# Capacitance_Sensing.net
KiCad netlist of a schematic drawn in Altium Designer
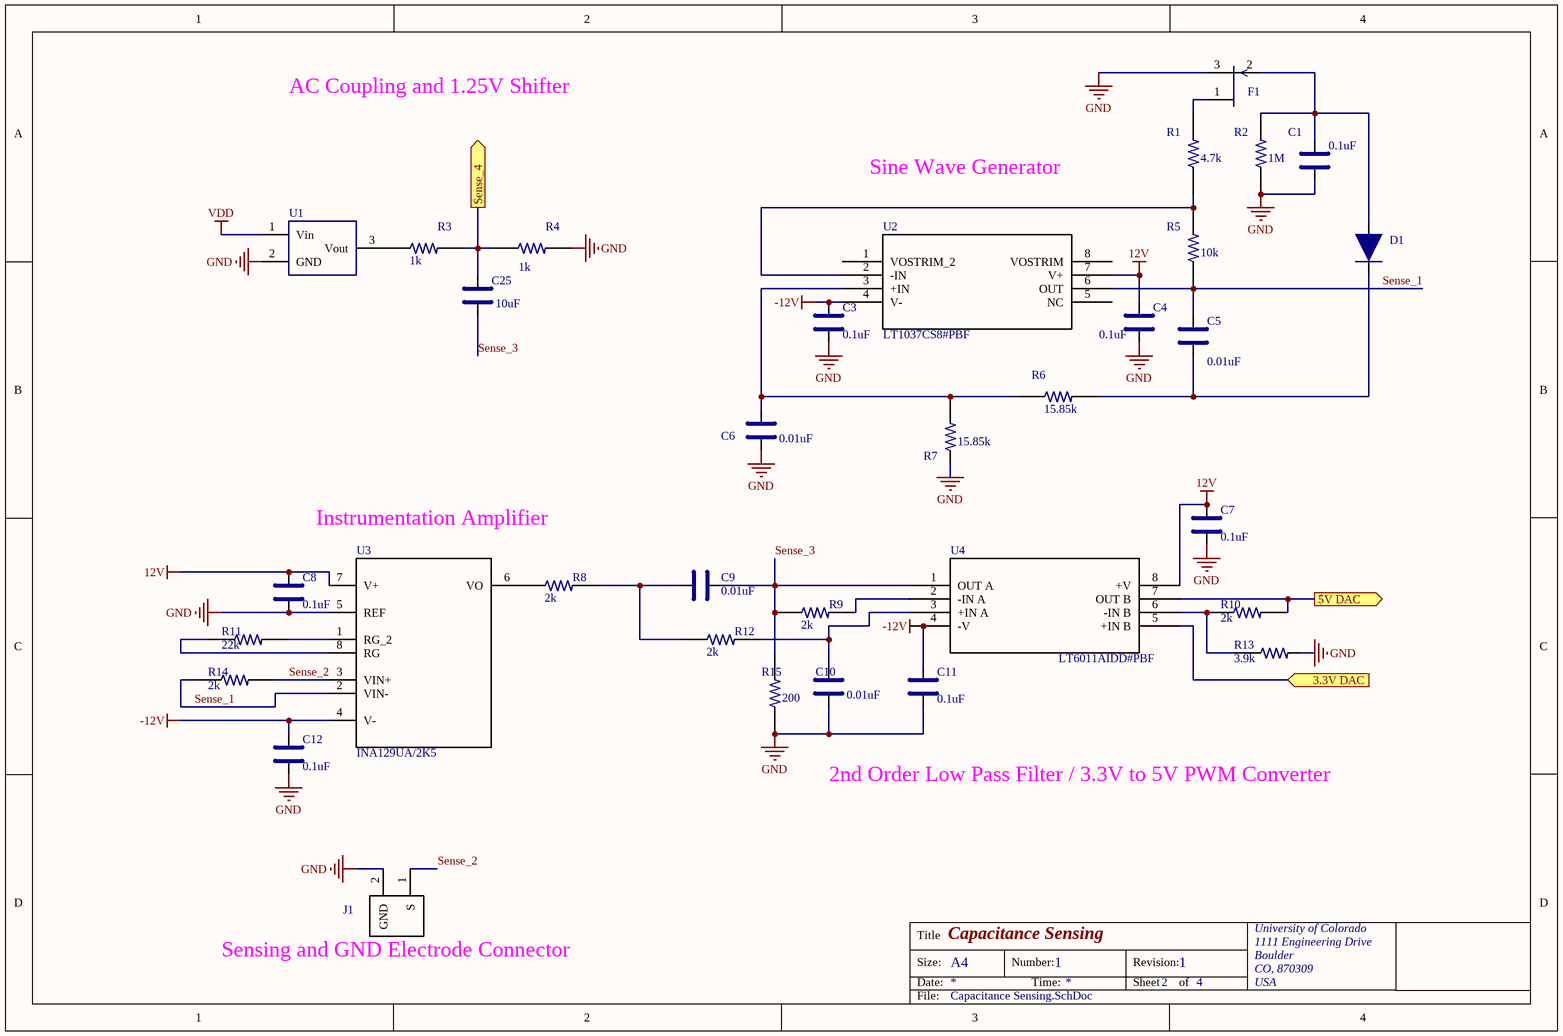
[diagram p0: Capacitance Sensing.SchDoc]

(export (version "E")
  (design (tool "Eeschema 10.0.6"))
  (components
    (comp (ref "C1")
      (value "0.1uF")
      (footprint "CL03A104KA3NNNC")
      (description "CAP CER 0.1UF 25V X5R 0201")
      (fields
        (field (name "MANUFACTURER") "Samsung")
        (field (name "MANUFACTURER PART NUMBER") "CL03A104KA3NNNC")
      )
      (libsource (lib "Sensing PEANO_Library") (part "CL03A104KA3NNNC"))
    )
    (comp (ref "C3")
      (value "0.1uF")
      (footprint "CL03A104KA3NNNC")
      (description "CAP CER 0.1UF 25V X5R 0201")
      (fields
        (field (name "MANUFACTURER") "Samsung")
        (field (name "MANUFACTURER PART NUMBER") "CL03A104KA3NNNC")
      )
      (libsource (lib "Sensing PEANO_Library") (part "CL03A104KA3NNNC"))
    )
    (comp (ref "C4")
      (value "0.1uF")
      (footprint "CL03A104KA3NNNC")
      (description "CAP CER 0.1UF 25V X5R 0201")
      (fields
        (field (name "MANUFACTURER") "Samsung")
        (field (name "MANUFACTURER PART NUMBER") "CL03A104KA3NNNC")
      )
      (libsource (lib "Sensing PEANO_Library") (part "CL03A104KA3NNNC"))
    )
    (comp (ref "C5")
      (value "0.01uF")
      (footprint "CL03B103KP3NNNC")
      (description "CAP CER 10000PF 10V X7R 0201")
      (fields
        (field (name "MANUFACTURER") "Samsung")
        (field (name "MANUFACTURER PART NUMBER") "CL03B103KP3NNNC")
      )
      (libsource (lib "Sensing PEANO_Library") (part "CL03B103KP3NNNC"))
    )
    (comp (ref "C6")
      (value "0.01uF")
      (footprint "CL03B103KP3NNNC")
      (description "CAP CER 10000PF 10V X7R 0201")
      (fields
        (field (name "MANUFACTURER") "Samsung")
        (field (name "MANUFACTURER PART NUMBER") "CL03B103KP3NNNC")
      )
      (libsource (lib "Sensing PEANO_Library") (part "CL03B103KP3NNNC"))
    )
    (comp (ref "C7")
      (value "0.1uF")
      (footprint "CL03A104KA3NNNC")
      (description "CAP CER 0.1UF 25V X5R 0201")
      (fields
        (field (name "MANUFACTURER") "Samsung")
        (field (name "MANUFACTURER PART NUMBER") "CL03A104KA3NNNC")
      )
      (libsource (lib "Sensing PEANO_Library") (part "CL03A104KA3NNNC"))
    )
    (comp (ref "C8")
      (value "0.1uF")
      (footprint "CL03A104KA3NNNC")
      (description "CAP CER 0.1UF 25V X5R 0201")
      (fields
        (field (name "MANUFACTURER") "Samsung")
        (field (name "MANUFACTURER PART NUMBER") "CL03A104KA3NNNC")
      )
      (libsource (lib "Sensing PEANO_Library") (part "CL03A104KA3NNNC"))
    )
    (comp (ref "C9")
      (value "0.01uF")
      (footprint "CL03B103KP3NNNC")
      (description "CAP CER 10000PF 10V X7R 0201")
      (fields
        (field (name "MANUFACTURER") "Samsung")
        (field (name "MANUFACTURER PART NUMBER") "CL03B103KP3NNNC")
      )
      (libsource (lib "Sensing PEANO_Library") (part "CL03B103KP3NNNC"))
    )
    (comp (ref "C10")
      (value "0.01uF")
      (footprint "CL03B103KP3NNNC")
      (description "CAP CER 10000PF 10V X7R 0201")
      (fields
        (field (name "MANUFACTURER") "Samsung")
        (field (name "MANUFACTURER PART NUMBER") "CL03B103KP3NNNC")
      )
      (libsource (lib "Sensing PEANO_Library") (part "CL03B103KP3NNNC"))
    )
    (comp (ref "C11")
      (value "0.1uF")
      (footprint "CL03A104KA3NNNC")
      (description "CAP CER 0.1UF 25V X5R 0201")
      (fields
        (field (name "MANUFACTURER") "Samsung")
        (field (name "MANUFACTURER PART NUMBER") "CL03A104KA3NNNC")
      )
      (libsource (lib "Sensing PEANO_Library") (part "CL03A104KA3NNNC"))
    )
    (comp (ref "C12")
      (value "0.1uF")
      (footprint "CL03A104KA3NNNC")
      (description "CAP CER 0.1UF 25V X5R 0201")
      (fields
        (field (name "MANUFACTURER") "Samsung")
        (field (name "MANUFACTURER PART NUMBER") "CL03A104KA3NNNC")
      )
      (libsource (lib "Sensing PEANO_Library") (part "CL03A104KA3NNNC"))
    )
    (comp (ref "C25")
      (value "10uF")
      (footprint "GRM155R60J106ME47D")
      (description "CAP CER 10UF 6.3V X5R 0402")
      (fields
        (field (name "MANUFACTURER") "Murata")
        (field (name "MANUFACTURER PART NUMBER") "GRM155R60J106ME47D")
      )
      (libsource (lib "Sensing PEANO_Library") (part "GRM155R60J106ME47D"))
    )
    (comp (ref "D1")
      (value "1N4148W-7-F")
      (footprint "1N4148W-7-F")
      (description "DIODE GEN PURP 100V 300MA SOD123")
      (fields
        (field (name "MANUFACTURER") "Diodes Incorporated")
        (field (name "DIGIKEY PART NUMBER") "1N4148W-FDICT-ND")
      )
      (libsource (lib "Sensing PEANO_Library") (part "1N4148W-7-F"))
    )
    (comp (ref "F1")
      (value "U309")
      (footprint "U309")
      (description "JFET JFET N-Channel -25V 20mA 500mW 4mW")
      (fields (field (name "MANUFACTURER") "InterFET") (field (name "DIGIKEY PART NUMBER") "106-U309"))
      (libsource (lib "Sensing PEANO_Library") (part "U309"))
    )
    (comp (ref "J1")
      (value "SM02B-SRSS-TB")
      (footprint "SM02B-SRSS-TB(LF)(SN)")
      (description "SH Series 2 Position 1 mm Pitch Surface Mount Side Entry Shrouded Header")
      (fields (field (name "MP") "SM02B-SRSS-TB_LF__SN_") (field (name "MF") "JST"))
      (libsource (lib "Sensing PEANO_Library") (part "SM02B-SRSS-TB(LF)(SN)"))
    )
    (comp (ref "R1")
      (value "4.7k")
      (footprint "RC0603J472CS")
      (description "RES SMD 4.7K OHM 5% 1/20W 0201")
      (fields
        (field (name "MANUFACTURER") "Samsung")
        (field (name "MANUFACTURER PART NUMBER") "RC0603J472CS")
      )
      (libsource (lib "Sensing PEANO_Library") (part "RC0603J472CS"))
    )
    (comp (ref "R2")
      (value "1M")
      (footprint "AC0201FR-071ML")
      (description "RES SMD 1M OHM 1% 1/20W 0201")
      (fields
        (field (name "MANUFACTURER") "Yageo")
        (field (name "MANUFACTURER PART NUMBER") "AC0201FR-071ML")
      )
      (libsource (lib "Sensing PEANO_Library") (part "AC0201FR-071ML"))
    )
    (comp (ref "R3")
      (value "1k")
      (footprint "RC0201FR-07130KL")
      (description "RES SMD 130K OHM 1% 1/20W 0201")
      (fields
        (field (name "MANUFACTURER") "Yageo")
        (field (name "MANUFACTURER PART NUMBER") "RC0201FR-07130KL")
      )
      (libsource (lib "Sensing PEANO_Library") (part "RC0201FR-07130KL"))
    )
    (comp (ref "R4")
      (value "1k")
      (footprint "RC0201FR-07130KL")
      (description "RES SMD 130K OHM 1% 1/20W 0201")
      (fields
        (field (name "MANUFACTURER") "Yageo")
        (field (name "MANUFACTURER PART NUMBER") "RC0201FR-07130KL")
      )
      (libsource (lib "Sensing PEANO_Library") (part "RC0201FR-07130KL"))
    )
    (comp (ref "R5")
      (value "10k")
      (footprint "RC0603F103CS")
      (description "RES SMD 10K OHM 1% 1/20W 0201")
      (fields
        (field (name "MANUFACTURER") "Samsung")
        (field (name "MANUFACTURER PART NUMBER") "RC0603F103CS")
      )
      (libsource (lib "Sensing PEANO_Library") (part "RC0603F103CS"))
    )
    (comp (ref "R6")
      (value "15.85k")
      (footprint "RMCF0201FT15K8")
      (description "RES 15.8K OHM 1% 1/20W 0201")
      (fields
        (field (name "MANUFACTURER") "Stackpole")
        (field (name "MANUFACTURER PART NUMBER") "RMCF0201FT15K8")
      )
      (libsource (lib "Sensing PEANO_Library") (part "RMCF0201FT15K8"))
    )
    (comp (ref "R7")
      (value "15.85k")
      (footprint "RMCF0201FT15K8")
      (description "RES 15.8K OHM 1% 1/20W 0201")
      (fields
        (field (name "MANUFACTURER") "Stackpole")
        (field (name "MANUFACTURER PART NUMBER") "RMCF0201FT15K8")
      )
      (libsource (lib "Sensing PEANO_Library") (part "RMCF0201FT15K8"))
    )
    (comp (ref "R8")
      (value "2k")
      (footprint "RC0603F202CS")
      (description "RES SMD 2K OHM 1% 1/20W 0201")
      (fields
        (field (name "MANUFACTURER") "Samsung")
        (field (name "MANUFACTURER PART NUMBER") "RC0603F202CS")
      )
      (libsource (lib "Sensing PEANO_Library") (part "RC0603F202CS"))
    )
    (comp (ref "R9")
      (value "2k")
      (footprint "RC0603F202CS")
      (description "RES SMD 2K OHM 1% 1/20W 0201")
      (fields
        (field (name "MANUFACTURER") "Samsung")
        (field (name "MANUFACTURER PART NUMBER") "RC0603F202CS")
      )
      (libsource (lib "Sensing PEANO_Library") (part "RC0603F202CS"))
    )
    (comp (ref "R10")
      (value "2k")
      (footprint "RC0603F202CS")
      (description "RES SMD 2K OHM 1% 1/20W 0201")
      (fields
        (field (name "MANUFACTURER") "Samsung")
        (field (name "MANUFACTURER PART NUMBER") "RC0603F202CS")
      )
      (libsource (lib "Sensing PEANO_Library") (part "RC0603F202CS"))
    )
    (comp (ref "R11")
      (value "22k")
      (footprint "ERJ-1GNJ223C")
      (description "RES SMD 22K OHM 5% 1/20W 0201")
      (fields
        (field (name "MANUFACTURER") "Samsung")
        (field (name "MANUFACTURER PART NUMBER") "ERJ-1GNJ223C")
      )
      (libsource (lib "Sensing PEANO_Library") (part "ERJ-1GNJ223C"))
    )
    (comp (ref "R12")
      (value "2k")
      (footprint "RC0603F202CS")
      (description "RES SMD 2K OHM 1% 1/20W 0201")
      (fields
        (field (name "MANUFACTURER") "Samsung")
        (field (name "MANUFACTURER PART NUMBER") "RC0603F202CS")
      )
      (libsource (lib "Sensing PEANO_Library") (part "RC0603F202CS"))
    )
    (comp (ref "R13")
      (value "3.9k")
      (footprint "RC0603F202CS")
      (description "RES SMD 2K OHM 1% 1/20W 0201")
      (fields
        (field (name "MANUFACTURER") "Samsung")
        (field (name "MANUFACTURER PART NUMBER") "RC0603F202CS")
      )
      (libsource (lib "Sensing PEANO_Library") (part "RC0603F202CS"))
    )
    (comp (ref "R14")
      (value "2k")
      (footprint "RC0603F202CS")
      (description "RES SMD 2K OHM 1% 1/20W 0201")
      (fields
        (field (name "MANUFACTURER") "Samsung")
        (field (name "MANUFACTURER PART NUMBER") "RC0603F202CS")
      )
      (libsource (lib "Sensing PEANO_Library") (part "RC0603F202CS"))
    )
    (comp (ref "R15")
      (value "200")
      (footprint "RC0603F202CS")
      (description "RES SMD 2K OHM 1% 1/20W 0201")
      (fields
        (field (name "MANUFACTURER") "Samsung")
        (field (name "MANUFACTURER PART NUMBER") "RC0603F202CS")
      )
      (libsource (lib "Sensing PEANO_Library") (part "RC0603F202CS"))
    )
    (comp (ref "U1")
      (value "ISL60002BIH325Z-T7A")
      (footprint "ISL60002-25")
      (description "IC VREF SERIES 2.5V SOT23-3")
      (fields
        (field (name "MANUFACTURER") "Renesas Electronics")
        (field (name "MANUFACTURER PART NUMBER") "ISL60002BIH325Z-TK")
      )
      (libsource (lib "Sensing PEANO_Library") (part "ISL60002BIH325Z-T7A"))
    )
    (comp (ref "U2")
      (value "LT1037CS8#PBF")
      (footprint "LT1037CS8#PBF")
      (description "IC OPAMP GP 60MHZ 8SO")
      (fields
        (field (name "MANUFACTURER") "Linear Technology")
        (field (name "DIGIKEY PART NUMBER") "LT1037CS8#PBF-ND")
      )
      (libsource (lib "Sensing PEANO_Library") (part "LT1037CS8#PBF"))
    )
    (comp (ref "U3")
      (value "INA129UA/2K5")
      (footprint "INA129UA/2K5")
      (description "IC OPAMP INSTR 1.3MHZ 8SOIC")
      (fields
        (field (name "MANUFACTURER") "Texas Instruments")
        (field (name "DIGIKEY PART NUMBER") "296-26058-1-ND")
      )
      (libsource (lib "Sensing PEANO_Library") (part "INA129UA/2K5"))
    )
    (comp (ref "U4")
      (value "LT6011AIDD#PBF")
      (footprint "ADP7104ACPZ-3.3-R7")
      (description "IC OPAMP GP 350KHZ RRO 8DFN")
      (fields
        (field (name "MANUFACTURER") "Analog Device")
        (field (name "DIGIKEY PART NUMBER") "LT6011AIDD#PBF-ND")
      )
      (libsource (lib "Sensing PEANO_Library") (part "LT6011AIDD#PBF"))
    )
  )
  (nets
    (net (code "1") (name "-12V") (class "Default")
      (node (ref "C11") (pin "1") (pinfunction "1_1") (pintype "passive"))
      (node (ref "C12") (pin "1") (pinfunction "1_1") (pintype "passive"))
      (node (ref "C3") (pin "1") (pinfunction "1_1") (pintype "passive"))
      (node (ref "U2") (pin "4") (pinfunction "V-_4") (pintype "passive"))
      (node (ref "U3") (pin "4") (pinfunction "V-_4") (pintype "passive"))
      (node (ref "U4") (pin "4") (pinfunction "-V_4") (pintype "passive"))
    )
    (net (code "2") (name "/3.3V DAC") (class "Default")
      (node (ref "U4") (pin "5") (pinfunction "+IN_B_5") (pintype "passive"))
    )
    (net (code "3") (name "/5V DAC") (class "Default")
      (node (ref "R10") (pin "1") (pinfunction "1_1") (pintype "passive"))
      (node (ref "U4") (pin "7") (pinfunction "OUT_B_7") (pintype "passive"))
    )
    (net (code "4") (name "/Sense_1") (class "Default")
      (node (ref "C5") (pin "1") (pinfunction "1_1") (pintype "passive"))
      (node (ref "R14") (pin "2") (pinfunction "2_2") (pintype "passive"))
      (node (ref "R5") (pin "2") (pinfunction "2_2") (pintype "passive"))
      (node (ref "U2") (pin "6") (pinfunction "OUT_6") (pintype "passive"))
      (node (ref "U3") (pin "2") (pinfunction "VIN-_2") (pintype "passive"))
    )
    (net (code "5") (name "/Sense_2") (class "Default")
      (node (ref "J1") (pin "1") (pinfunction "S_1") (pintype "passive"))
      (node (ref "R14") (pin "1") (pinfunction "1_1") (pintype "passive"))
      (node (ref "U3") (pin "3") (pinfunction "VIN+_3") (pintype "passive"))
    )
    (net (code "6") (name "/Sense_3") (class "Default")
      (node (ref "C25") (pin "2") (pinfunction "2_2") (pintype "passive"))
      (node (ref "C9") (pin "1") (pinfunction "1_1") (pintype "passive"))
      (node (ref "R15") (pin "1") (pinfunction "1_1") (pintype "passive"))
      (node (ref "R9") (pin "2") (pinfunction "2_2") (pintype "passive"))
      (node (ref "U4") (pin "1") (pinfunction "OUT_A_1") (pintype "passive"))
    )
    (net (code "7") (name "/Sense_4") (class "Default")
      (node (ref "C25") (pin "1") (pinfunction "1_1") (pintype "passive"))
      (node (ref "R3") (pin "1") (pinfunction "1_1") (pintype "passive"))
      (node (ref "R4") (pin "2") (pinfunction "2_2") (pintype "passive"))
    )
    (net (code "8") (name "12V") (class "Default")
      (node (ref "C4") (pin "1") (pinfunction "1_1") (pintype "passive"))
      (node (ref "C7") (pin "1") (pinfunction "1_1") (pintype "passive"))
      (node (ref "C8") (pin "1") (pinfunction "1_1") (pintype "passive"))
      (node (ref "U2") (pin "7") (pinfunction "V+_7") (pintype "passive"))
      (node (ref "U3") (pin "7") (pinfunction "V+_7") (pintype "passive"))
      (node (ref "U4") (pin "8") (pinfunction "+V_8") (pintype "passive"))
    )
    (net (code "9") (name "GND") (class "Default")
      (node (ref "C1") (pin "2") (pinfunction "2_2") (pintype "passive"))
      (node (ref "C10") (pin "2") (pinfunction "2_2") (pintype "passive"))
      (node (ref "C11") (pin "2") (pinfunction "2_2") (pintype "passive"))
      (node (ref "C12") (pin "2") (pinfunction "2_2") (pintype "passive"))
      (node (ref "C3") (pin "2") (pinfunction "2_2") (pintype "passive"))
      (node (ref "C4") (pin "2") (pinfunction "2_2") (pintype "passive"))
      (node (ref "C6") (pin "2") (pinfunction "2_2") (pintype "passive"))
      (node (ref "C7") (pin "2") (pinfunction "2_2") (pintype "passive"))
      (node (ref "C8") (pin "2") (pinfunction "2_2") (pintype "passive"))
      (node (ref "F1") (pin "3") (pinfunction "S_3") (pintype "passive"))
      (node (ref "J1") (pin "2") (pinfunction "GND_2") (pintype "passive"))
      (node (ref "R13") (pin "1") (pinfunction "1_1") (pintype "passive"))
      (node (ref "R15") (pin "2") (pinfunction "2_2") (pintype "passive"))
      (node (ref "R2") (pin "2") (pinfunction "2_2") (pintype "passive"))
      (node (ref "R4") (pin "1") (pinfunction "1_1") (pintype "passive"))
      (node (ref "R7") (pin "2") (pinfunction "2_2") (pintype "passive"))
      (node (ref "U1") (pin "2") (pinfunction "GND_2") (pintype "passive"))
      (node (ref "U3") (pin "5") (pinfunction "REF_5") (pintype "passive"))
    )
    (net (code "10") (name "Net-(C5-Pad2)") (class "Default")
      (node (ref "C5") (pin "2") (pinfunction "2_2") (pintype "passive"))
      (node (ref "D1") (pin "1") (pinfunction "1_1") (pintype "passive"))
      (node (ref "R6") (pin "1") (pinfunction "1_1") (pintype "passive"))
    )
    (net (code "11") (name "Net-(C9-Pad2)") (class "Default")
      (node (ref "C9") (pin "2") (pinfunction "2_2") (pintype "passive"))
      (node (ref "R12") (pin "2") (pinfunction "2_2") (pintype "passive"))
      (node (ref "R8") (pin "1") (pinfunction "1_1") (pintype "passive"))
    )
    (net (code "12") (name "Net-(F1-D)") (class "Default")
      (node (ref "F1") (pin "1") (pinfunction "D_1") (pintype "passive"))
      (node (ref "R1") (pin "1") (pinfunction "1_1") (pintype "passive"))
    )
    (net (code "13") (name "Net-(F1-G)") (class "Default")
      (node (ref "C1") (pin "1") (pinfunction "1_1") (pintype "passive"))
      (node (ref "D1") (pin "2") (pinfunction "2_2") (pintype "passive"))
      (node (ref "F1") (pin "2") (pinfunction "G_2") (pintype "passive"))
      (node (ref "R2") (pin "1") (pinfunction "1_1") (pintype "passive"))
    )
    (net (code "14") (name "Net-(U1-Vout)") (class "Default")
      (node (ref "R3") (pin "2") (pinfunction "2_2") (pintype "passive"))
      (node (ref "U1") (pin "3") (pinfunction "Vout_3") (pintype "passive"))
    )
    (net (code "15") (name "Net-(U2-+IN)") (class "Default")
      (node (ref "C6") (pin "1") (pinfunction "1_1") (pintype "passive"))
      (node (ref "R6") (pin "2") (pinfunction "2_2") (pintype "passive"))
      (node (ref "R7") (pin "1") (pinfunction "1_1") (pintype "passive"))
      (node (ref "U2") (pin "3") (pinfunction "+IN_3") (pintype "passive"))
    )
    (net (code "16") (name "Net-(U2--IN)") (class "Default")
      (node (ref "R1") (pin "2") (pinfunction "2_2") (pintype "passive"))
      (node (ref "R5") (pin "1") (pinfunction "1_1") (pintype "passive"))
      (node (ref "U2") (pin "2") (pinfunction "-IN_2") (pintype "passive"))
    )
    (net (code "17") (name "Net-(U3-RG)") (class "Default")
      (node (ref "R11") (pin "2") (pinfunction "2_2") (pintype "passive"))
      (node (ref "U3") (pin "8") (pinfunction "RG_8") (pintype "passive"))
    )
    (net (code "18") (name "Net-(U3-RG_2)") (class "Default")
      (node (ref "R11") (pin "1") (pinfunction "1_1") (pintype "passive"))
      (node (ref "U3") (pin "1") (pinfunction "RG_2_1") (pintype "passive"))
    )
    (net (code "19") (name "Net-(U3-VO)") (class "Default")
      (node (ref "R8") (pin "2") (pinfunction "2_2") (pintype "passive"))
      (node (ref "U3") (pin "6") (pinfunction "VO_6") (pintype "passive"))
    )
    (net (code "20") (name "Net-(U4-+IN_A)") (class "Default")
      (node (ref "C10") (pin "1") (pinfunction "1_1") (pintype "passive"))
      (node (ref "R12") (pin "1") (pinfunction "1_1") (pintype "passive"))
      (node (ref "U4") (pin "3") (pinfunction "+IN_A_3") (pintype "passive"))
    )
    (net (code "21") (name "Net-(U4--IN_A)") (class "Default")
      (node (ref "R9") (pin "1") (pinfunction "1_1") (pintype "passive"))
      (node (ref "U4") (pin "2") (pinfunction "-IN_A_2") (pintype "passive"))
    )
    (net (code "22") (name "Net-(U4--IN_B)") (class "Default")
      (node (ref "R10") (pin "2") (pinfunction "2_2") (pintype "passive"))
      (node (ref "R13") (pin "2") (pinfunction "2_2") (pintype "passive"))
      (node (ref "U4") (pin "6") (pinfunction "-IN_B_6") (pintype "passive"))
    )
    (net (code "23") (name "VDD") (class "Default")
      (node (ref "U1") (pin "1") (pinfunction "Vin_1") (pintype "passive"))
    )
    (net (code "24") (name "unconnected-(U2-NC-Pad5)") (class "Default")
      (node (ref "U2") (pin "5") (pinfunction "NC_5") (pintype "passive"))
    )
    (net (code "25") (name "unconnected-(U2-VOSTRIM-Pad8)") (class "Default")
      (node (ref "U2") (pin "8") (pinfunction "VOSTRIM_8") (pintype "passive"))
    )
    (net (code "26") (name "unconnected-(U2-VOSTRIM_2-Pad1)") (class "Default")
      (node (ref "U2") (pin "1") (pinfunction "VOSTRIM_2_1") (pintype "passive"))
    )
  )
)
